# Sheet1.net
KiCad netlist of a schematic drawn in Altium Designer
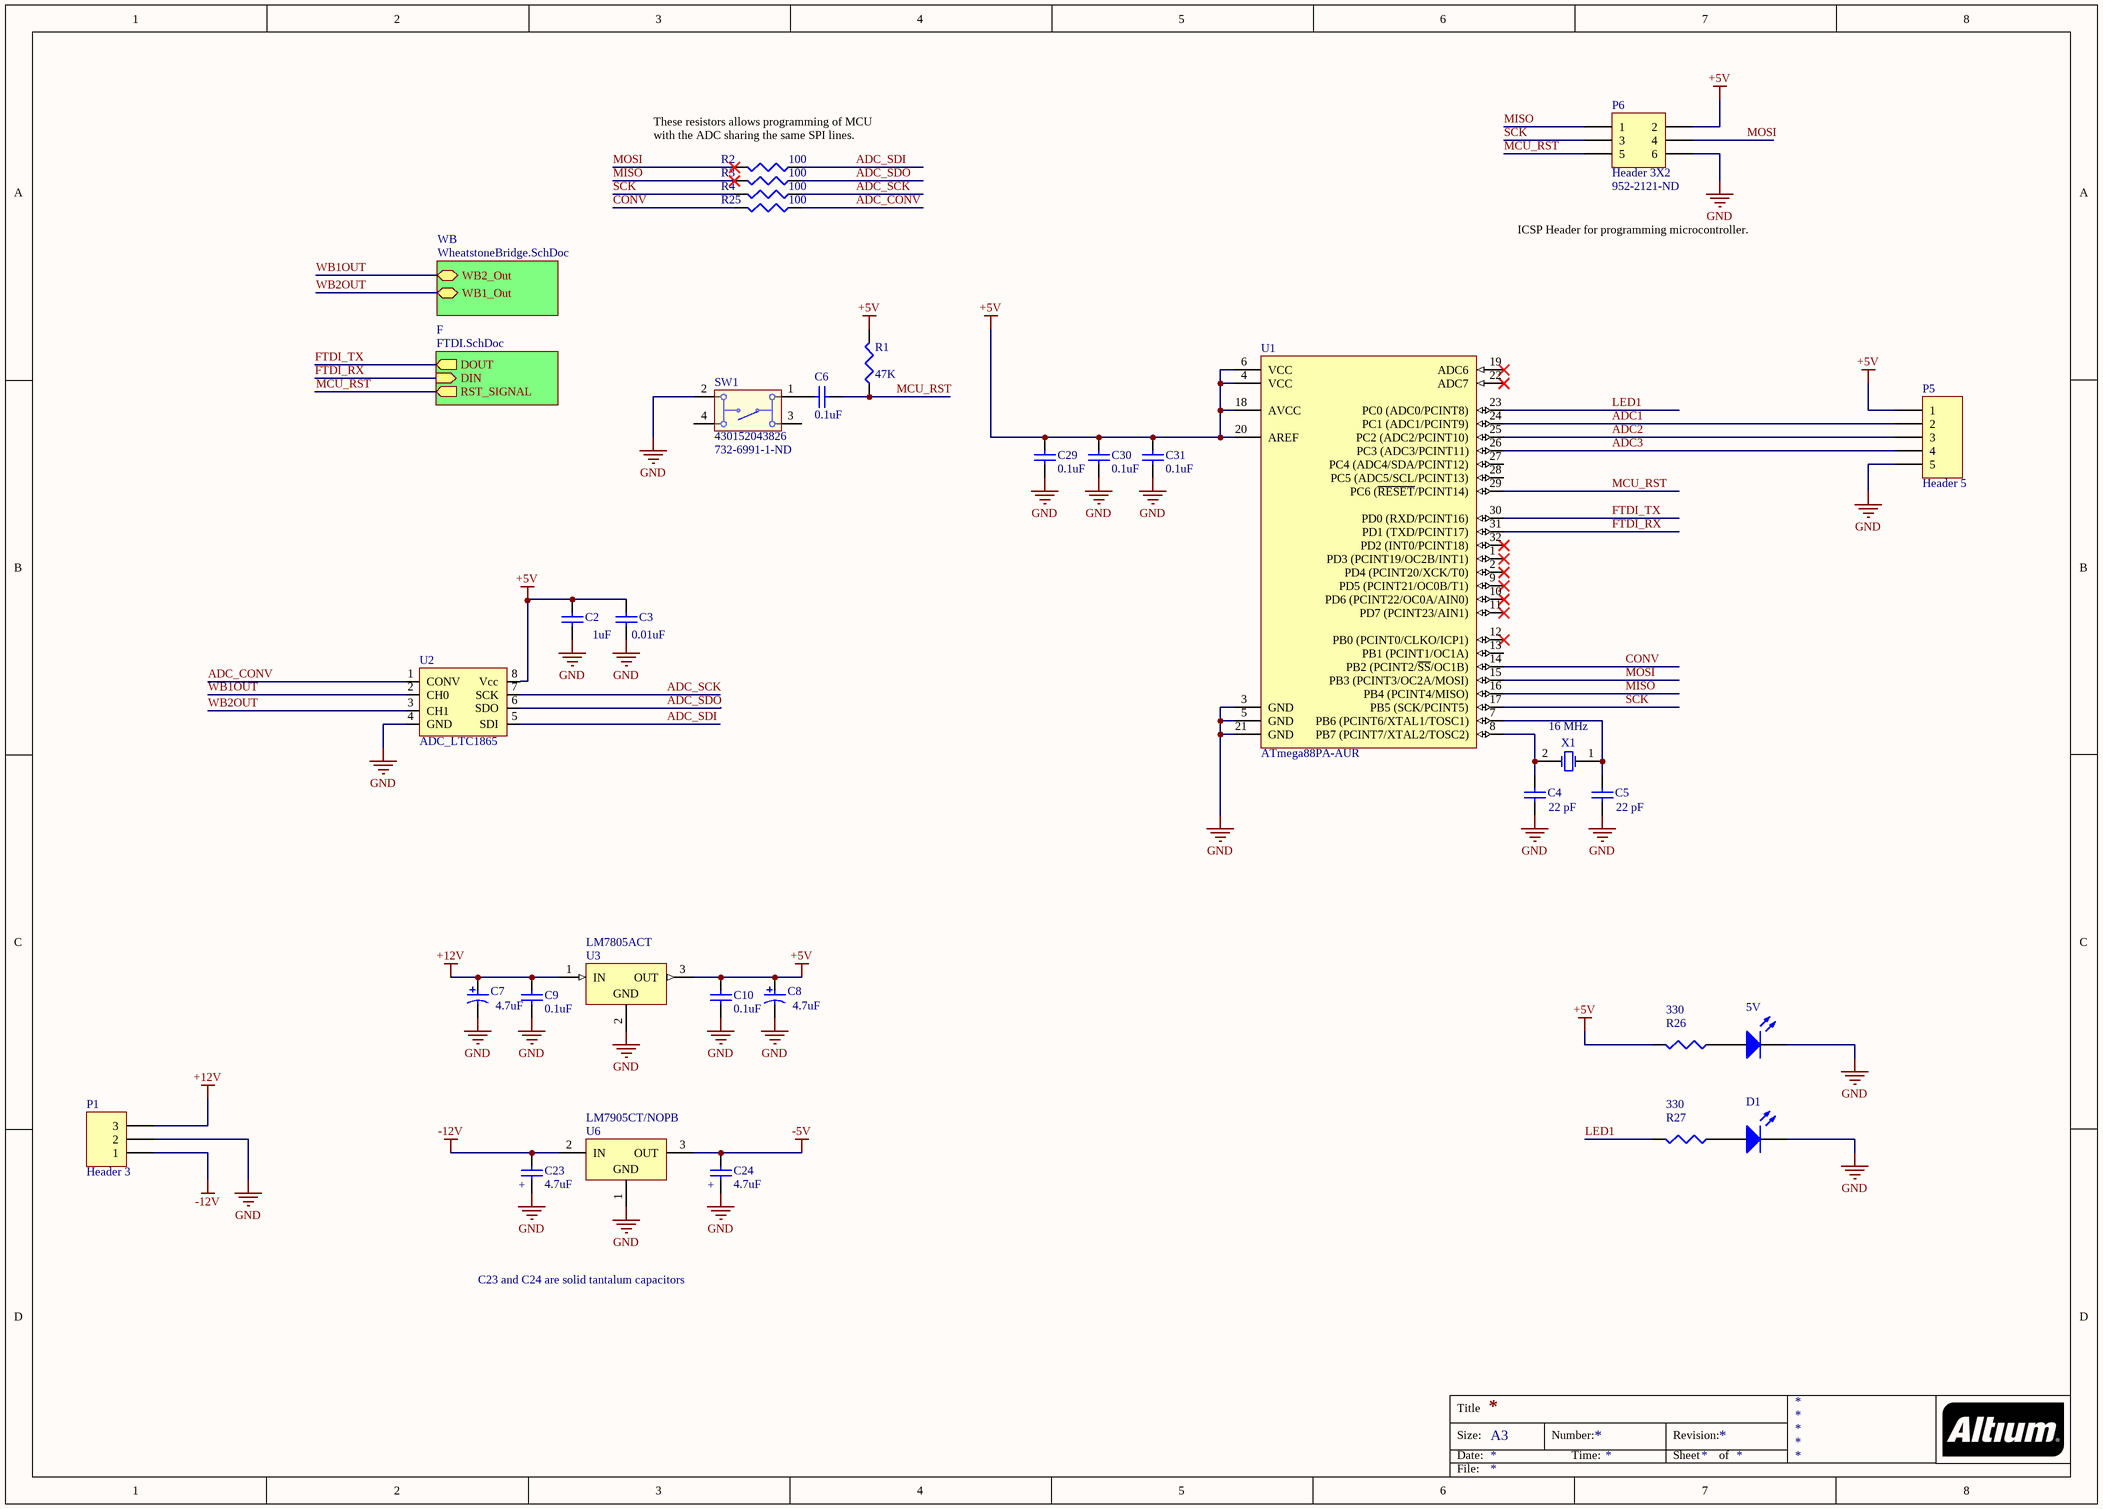
[diagram p0: Sheet1.SchDoc]

(export (version "E")
  (design (tool "Eeschema 10.0.6"))
  (components
    (comp (ref "5V")
      (value "150060RS75000")
      (footprint "0603_A")
      (description "SMD mono-color Chip LED, WL-SMCW, Red")
      (fields (field (name "MANUFACTURER") "Wuerth Elektronik"))
      (libsource (lib "Altium Content Vault") (part "CMP-1426-00001-1"))
    )
    (comp (ref "C2")
      (value "1uF")
      (footprint "1608[0603]")
      (description "Capacitor (Semiconductor SIM Model)")
      (fields (field (name "Comment") "Cap Semi") (field (name "PUBLISHER") "Altium Limited"))
      (libsource (lib "Miscellaneous Devices") (part "Cap Semi"))
    )
    (comp (ref "C3")
      (value "0.01uF")
      (footprint "1608[0603]")
      (description "Capacitor (Semiconductor SIM Model)")
      (fields (field (name "Comment") "Cap Semi") (field (name "PUBLISHER") "Altium Limited"))
      (libsource (lib "Miscellaneous Devices") (part "Cap Semi"))
    )
    (comp (ref "C4")
      (value "22 pF")
      (footprint "1608[0603]")
      (description "Capacitor (Semiconductor SIM Model)")
      (fields (field (name "Comment") "Cap Semi") (field (name "PUBLISHER") "Altium Limited"))
      (libsource (lib "Miscellaneous Devices") (part "Cap Semi"))
    )
    (comp (ref "C5")
      (value "22 pF")
      (footprint "1608[0603]")
      (description "Capacitor (Semiconductor SIM Model)")
      (fields (field (name "Comment") "Cap Semi") (field (name "PUBLISHER") "Altium Limited"))
      (libsource (lib "Miscellaneous Devices") (part "Cap Semi"))
    )
    (comp (ref "C6")
      (value "0.1uF")
      (footprint "1608[0603]")
      (description "Capacitor (Semiconductor SIM Model)")
      (fields (field (name "Comment") "Cap Semi") (field (name "PUBLISHER") "Altium Limited"))
      (libsource (lib "Miscellaneous Devices") (part "Cap Semi"))
    )
    (comp (ref "C7")
      (value "TAJA475K016RNJ")
      (footprint "AVX-TAJ-A-2_N")
      (description "Standard Tantalum, 4.7 uF, +/- 10%, 16 V, -55 to 125 degC, 2-Pin SMD (1206), RoHS, Tape and Reel")
      (fields
        (field (name "TOLERANCE") "10%")
        (field (name "VOLTAGE") "16V")
        (field (name "CAPACITANCE") "4.7uF")
      )
      (libsource (lib "Altium Content Vault") (part "CMP-2100-03687-1"))
    )
    (comp (ref "C8")
      (value "TAJA475K016RNJ")
      (footprint "AVX-TAJ-A-2_N")
      (description "Standard Tantalum, 4.7 uF, +/- 10%, 16 V, -55 to 125 degC, 2-Pin SMD (1206), RoHS, Tape and Reel")
      (fields
        (field (name "TOLERANCE") "10%")
        (field (name "VOLTAGE") "16V")
        (field (name "CAPACITANCE") "4.7uF")
      )
      (libsource (lib "Altium Content Vault") (part "CMP-2100-03687-1"))
    )
    (comp (ref "C9")
      (value "0.1uF")
      (footprint "1608[0603]")
      (description "Capacitor (Semiconductor SIM Model)")
      (fields (field (name "Comment") "Cap Semi") (field (name "PUBLISHER") "Altium Limited"))
      (libsource (lib "Miscellaneous Devices") (part "Cap Semi"))
    )
    (comp (ref "C10")
      (value "0.1uF")
      (footprint "1608[0603]")
      (description "Capacitor (Semiconductor SIM Model)")
      (fields (field (name "Comment") "Cap Semi") (field (name "PUBLISHER") "Altium Limited"))
      (libsource (lib "Miscellaneous Devices") (part "Cap Semi"))
    )
    (comp (ref "C23")
      (value "4.7uF")
      (footprint "1608[0603]")
      (description "Capacitor (Semiconductor SIM Model)")
      (fields (field (name "Comment") "Cap Semi") (field (name "PUBLISHER") "Altium Limited"))
      (libsource (lib "Miscellaneous Devices") (part "Cap Semi"))
    )
    (comp (ref "C24")
      (value "4.7uF")
      (footprint "1608[0603]")
      (description "Capacitor (Semiconductor SIM Model)")
      (fields (field (name "Comment") "Cap Semi") (field (name "PUBLISHER") "Altium Limited"))
      (libsource (lib "Miscellaneous Devices") (part "Cap Semi"))
    )
    (comp (ref "C29")
      (value "0.1uF")
      (footprint "1608[0603]")
      (description "Capacitor (Semiconductor SIM Model)")
      (fields (field (name "Comment") "Cap Semi") (field (name "PUBLISHER") "Altium Limited"))
      (libsource (lib "Miscellaneous Devices") (part "Cap Semi"))
    )
    (comp (ref "C30")
      (value "0.1uF")
      (footprint "1608[0603]")
      (description "Capacitor (Semiconductor SIM Model)")
      (fields (field (name "Comment") "Cap Semi") (field (name "PUBLISHER") "Altium Limited"))
      (libsource (lib "Miscellaneous Devices") (part "Cap Semi"))
    )
    (comp (ref "C31")
      (value "0.1uF")
      (footprint "1608[0603]")
      (description "Capacitor (Semiconductor SIM Model)")
      (fields (field (name "Comment") "Cap Semi") (field (name "PUBLISHER") "Altium Limited"))
      (libsource (lib "Miscellaneous Devices") (part "Cap Semi"))
    )
    (comp (ref "D1")
      (value "150060RS75000")
      (footprint "0603_A")
      (description "SMD mono-color Chip LED, WL-SMCW, Red")
      (fields (field (name "MANUFACTURER") "Wuerth Elektronik"))
      (libsource (lib "Altium Content Vault") (part "CMP-1426-00001-1"))
    )
    (comp (ref "P1")
      (value "Header 3")
      (footprint "HDR1X3")
      (description "Header, 3-Pin")
      (fields (field (name "PUBLISHER") "Altium Limited"))
      (libsource (lib "Miscellaneous Connectors") (part "Header 3"))
    )
    (comp (ref "P5")
      (value "Header 5")
      (footprint "HDR1X5")
      (description "Header, 5-Pin")
      (fields (field (name "PUBLISHER") "Altium Limited"))
      (libsource (lib "Miscellaneous Connectors") (part "Header 5"))
    )
    (comp (ref "P6")
      (value "Header 3X2")
      (footprint "HDR2X3")
      (description "Header, 3-Pin, Dual row")
      (fields
        (field (name "SUPPLIER PART NUMBER 1") "952-2121-ND")
        (field (name "PUBLISHER") "Altium Limited")
      )
      (libsource (lib "Miscellaneous Connectors") (part "Header 3X2"))
    )
    (comp (ref "R1")
      (value "47K")
      (footprint "J1-0603")
      (description "Resistor")
      (fields (field (name "Comment") "Res3") (field (name "PUBLISHER") "Altium Limited"))
      (libsource (lib "Miscellaneous Devices") (part "Res3"))
    )
    (comp (ref "R2")
      (value "100")
      (footprint "J1-0603")
      (description "Resistor")
      (fields (field (name "Comment") "Res3") (field (name "PUBLISHER") "Altium Limited"))
      (libsource (lib "Miscellaneous Devices") (part "Res3"))
    )
    (comp (ref "R3")
      (value "100")
      (footprint "J1-0603")
      (description "Resistor")
      (fields (field (name "Comment") "Res3") (field (name "PUBLISHER") "Altium Limited"))
      (libsource (lib "Miscellaneous Devices") (part "Res3"))
    )
    (comp (ref "R4")
      (value "100")
      (footprint "J1-0603")
      (description "Resistor")
      (fields (field (name "Comment") "Res3") (field (name "PUBLISHER") "Altium Limited"))
      (libsource (lib "Miscellaneous Devices") (part "Res3"))
    )
    (comp (ref "R25")
      (value "100")
      (footprint "J1-0603")
      (description "Resistor")
      (fields (field (name "Comment") "Res3") (field (name "PUBLISHER") "Altium Limited"))
      (libsource (lib "Miscellaneous Devices") (part "Res3"))
    )
    (comp (ref "R26")
      (value "330")
      (footprint "J1-0603")
      (description "Resistor")
      (fields (field (name "Comment") "Res3") (field (name "PUBLISHER") "Altium Limited"))
      (libsource (lib "Miscellaneous Devices") (part "Res3"))
    )
    (comp (ref "R27")
      (value "330")
      (footprint "J1-0603")
      (description "Resistor")
      (fields (field (name "Comment") "Res3") (field (name "PUBLISHER") "Altium Limited"))
      (libsource (lib "Miscellaneous Devices") (part "Res3"))
    )
    (comp (ref "SW1")
      (value "430152043826")
      (footprint "430152043826")
      (description "WS-TASV SMD Tact Switch 6X6 mm")
      (fields
        (field (name "MANUFACTURER") "Wuerth Elektronik")
        (field (name "SUPPLIER PART NUMBER 1") "732-6991-1-ND")
      )
      (libsource (lib "Altium Content Vault") (part "WE-TACT-SW-4"))
    )
    (comp (ref "U1")
      (value "ATmega88PA-AUR")
      (footprint "32A_N")
      (libsource (lib "Altium Content Vault") (part "MC-8B-ATM48-SQ32"))
    )
    (comp (ref "U2")
      (value "ADC_LTC1865")
      (footprint "PcbLib1:LTC1865_SOIC8")
      (libsource (lib "Schlib1") (part "ADC_LTC1865"))
    )
    (comp (ref "U3")
      (value "LM7805ACT")
      (footprint "FAIR-TO-220-3")
      (description "Positive Voltage Regulator, 5 V, 1 A, 0 to 125 degC, 3-Pin TO-220, RoHS, Tube")
      (fields (field (name "MANUFACTURER") "Fairchild"))
      (libsource (lib "Altium Content Vault") (part "FAIR-LM7805CT-TO220-3"))
    )
    (comp (ref "U6")
      (value "LM7905CT/NOPB")
      (footprint "NDE0003A")
      (description "3-Terminal Negative Regulator, 3-pin TO-220, Pb-Free")
      (fields (field (name "MANUFACTURER") "Texas Instruments"))
      (libsource (lib "Altium Content Vault") (part "PM-REG-LM7905-SIL3"))
    )
    (comp (ref "X1")
      (value "ABLS2-16.000MHZ-D4Y-T")
      (footprint "ABRA-ABLS2-2_V")
      (fields (field (name "MANUFACTURER") "Abracon") (field (name "FREQUENCY") "16 MHz"))
      (libsource (lib "Altium Content Vault") (part "CMP-0277-00002-1"))
    )
  )
  (nets
    (net (code "1") (name "+5V") (class "Default")
      (node (ref "C10") (pin "1") (pinfunction "1_1") (pintype "passive"))
      (node (ref "C2") (pin "1") (pinfunction "1_1") (pintype "passive"))
      (node (ref "C29") (pin "1") (pinfunction "1_1") (pintype "passive"))
      (node (ref "C3") (pin "1") (pinfunction "1_1") (pintype "passive"))
      (node (ref "C30") (pin "1") (pinfunction "1_1") (pintype "passive"))
      (node (ref "C31") (pin "1") (pinfunction "1_1") (pintype "passive"))
      (node (ref "C8") (pin "1") (pinfunction "1_1") (pintype "passive"))
      (node (ref "P5") (pin "1") (pinfunction "1_1") (pintype "passive"))
      (node (ref "P6") (pin "2") (pinfunction "2_2") (pintype "passive"))
      (node (ref "R1") (pin "2") (pinfunction "2_2") (pintype "passive"))
      (node (ref "R26") (pin "2") (pinfunction "2_2") (pintype "passive"))
      (node (ref "U1") (pin "18") (pinfunction "AVCC_18") (pintype "power_in"))
      (node (ref "U1") (pin "20") (pinfunction "AREF_20") (pintype "passive"))
      (node (ref "U1") (pin "4") (pinfunction "VCC_4") (pintype "power_in"))
      (node (ref "U1") (pin "6") (pinfunction "VCC_6") (pintype "power_in"))
      (node (ref "U2") (pin "8") (pinfunction "Vcc_8") (pintype "passive"))
      (node (ref "U3") (pin "3") (pinfunction "OUT_3") (pintype "output"))
    )
    (net (code "2") (name "+12V") (class "Default")
      (node (ref "C7") (pin "1") (pinfunction "1_1") (pintype "passive"))
      (node (ref "C9") (pin "1") (pinfunction "1_1") (pintype "passive"))
      (node (ref "P1") (pin "3") (pinfunction "3_3") (pintype "passive"))
      (node (ref "U3") (pin "1") (pinfunction "IN_1") (pintype "input"))
    )
    (net (code "3") (name "-5V") (class "Default")
      (node (ref "C24") (pin "1") (pinfunction "1_1") (pintype "passive"))
      (node (ref "U6") (pin "3") (pinfunction "OUT_3") (pintype "power_in"))
    )
    (net (code "4") (name "-12V") (class "Default")
      (node (ref "C23") (pin "1") (pinfunction "1_1") (pintype "passive"))
      (node (ref "P1") (pin "1") (pinfunction "1_1") (pintype "passive"))
      (node (ref "U6") (pin "2") (pinfunction "IN_2") (pintype "power_in"))
    )
    (net (code "5") (name "/ADC1") (class "Default")
      (node (ref "P5") (pin "2") (pinfunction "2_2") (pintype "passive"))
      (node (ref "U1") (pin "24") (pinfunction "PC1_(ADC1/PCINT9)_24") (pintype "bidirectional"))
    )
    (net (code "6") (name "/ADC2") (class "Default")
      (node (ref "P5") (pin "3") (pinfunction "3_3") (pintype "passive"))
      (node (ref "U1") (pin "25") (pinfunction "PC2_(ADC2/PCINT10)_25") (pintype "bidirectional"))
    )
    (net (code "7") (name "/ADC3") (class "Default")
      (node (ref "P5") (pin "4") (pinfunction "4_4") (pintype "passive"))
      (node (ref "U1") (pin "26") (pinfunction "PC3_(ADC3/PCINT11)_26") (pintype "bidirectional"))
    )
    (net (code "8") (name "/ADC_CONV") (class "Default")
      (node (ref "R25") (pin "1") (pinfunction "1_1") (pintype "passive"))
      (node (ref "U2") (pin "1") (pinfunction "CONV_1") (pintype "passive"))
    )
    (net (code "9") (name "/ADC_SCK") (class "Default")
      (node (ref "R4") (pin "1") (pinfunction "1_1") (pintype "passive"))
      (node (ref "U2") (pin "7") (pinfunction "SCK_7") (pintype "passive"))
    )
    (net (code "10") (name "/ADC_SDI") (class "Default")
      (node (ref "R2") (pin "1") (pinfunction "1_1") (pintype "passive"))
      (node (ref "U2") (pin "5") (pinfunction "SDI_5") (pintype "passive"))
    )
    (net (code "11") (name "/ADC_SDO") (class "Default")
      (node (ref "R3") (pin "1") (pinfunction "1_1") (pintype "passive"))
      (node (ref "U2") (pin "6") (pinfunction "SDO_6") (pintype "passive"))
    )
    (net (code "12") (name "/CONV") (class "Default")
      (node (ref "R25") (pin "2") (pinfunction "2_2") (pintype "passive"))
      (node (ref "U1") (pin "14") (pinfunction "PB2_(PCINT2/~{SS}/OC1B)_14") (pintype "bidirectional"))
    )
    (net (code "13") (name "/FTDI_RX") (class "Default")
      (node (ref "U1") (pin "31") (pinfunction "PD1_(TXD/PCINT17)_31") (pintype "bidirectional"))
    )
    (net (code "14") (name "/FTDI_TX") (class "Default")
      (node (ref "U1") (pin "30") (pinfunction "PD0_(RXD/PCINT16)_30") (pintype "bidirectional"))
    )
    (net (code "15") (name "/LED1") (class "Default")
      (node (ref "R27") (pin "2") (pinfunction "2_2") (pintype "passive"))
      (node (ref "U1") (pin "23") (pinfunction "PC0_(ADC0/PCINT8)_23") (pintype "bidirectional"))
    )
    (net (code "16") (name "/MCU_RST") (class "Default")
      (node (ref "C6") (pin "1") (pinfunction "1_1") (pintype "passive"))
      (node (ref "P6") (pin "5") (pinfunction "5_5") (pintype "passive"))
      (node (ref "R1") (pin "1") (pinfunction "1_1") (pintype "passive"))
      (node (ref "U1") (pin "29") (pinfunction "PC6_(~{RESET}/PCINT14)_29") (pintype "bidirectional"))
    )
    (net (code "17") (name "/MISO") (class "Default")
      (node (ref "P6") (pin "1") (pinfunction "1_1") (pintype "passive"))
      (node (ref "R3") (pin "2") (pinfunction "2_2") (pintype "passive"))
      (node (ref "U1") (pin "16") (pinfunction "PB4_(PCINT4/MISO)_16") (pintype "bidirectional"))
    )
    (net (code "18") (name "/MOSI") (class "Default")
      (node (ref "P6") (pin "4") (pinfunction "4_4") (pintype "passive"))
      (node (ref "R2") (pin "2") (pinfunction "2_2") (pintype "passive"))
      (node (ref "U1") (pin "15") (pinfunction "PB3_(PCINT3/OC2A/MOSI)_15") (pintype "bidirectional"))
    )
    (net (code "19") (name "/SCK") (class "Default")
      (node (ref "P6") (pin "3") (pinfunction "3_3") (pintype "passive"))
      (node (ref "R4") (pin "2") (pinfunction "2_2") (pintype "passive"))
      (node (ref "U1") (pin "17") (pinfunction "PB5_(SCK/PCINT5)_17") (pintype "bidirectional"))
    )
    (net (code "20") (name "/WB1OUT") (class "Default")
      (node (ref "U2") (pin "2") (pinfunction "CH0_2") (pintype "passive"))
    )
    (net (code "21") (name "/WB2OUT") (class "Default")
      (node (ref "U2") (pin "3") (pinfunction "CH1_3") (pintype "passive"))
    )
    (net (code "22") (name "GND") (class "Default")
      (node (ref "5V") (pin "1") (pinfunction "K_1") (pintype "passive"))
      (node (ref "C10") (pin "2") (pinfunction "2_2") (pintype "passive"))
      (node (ref "C2") (pin "2") (pinfunction "2_2") (pintype "passive"))
      (node (ref "C23") (pin "2") (pinfunction "2_2") (pintype "passive"))
      (node (ref "C24") (pin "2") (pinfunction "2_2") (pintype "passive"))
      (node (ref "C29") (pin "2") (pinfunction "2_2") (pintype "passive"))
      (node (ref "C3") (pin "2") (pinfunction "2_2") (pintype "passive"))
      (node (ref "C30") (pin "2") (pinfunction "2_2") (pintype "passive"))
      (node (ref "C31") (pin "2") (pinfunction "2_2") (pintype "passive"))
      (node (ref "C4") (pin "1") (pinfunction "1_1") (pintype "passive"))
      (node (ref "C5") (pin "1") (pinfunction "1_1") (pintype "passive"))
      (node (ref "C7") (pin "2") (pinfunction "2_2") (pintype "passive"))
      (node (ref "C8") (pin "2") (pinfunction "2_2") (pintype "passive"))
      (node (ref "C9") (pin "2") (pinfunction "2_2") (pintype "passive"))
      (node (ref "D1") (pin "1") (pinfunction "K_1") (pintype "passive"))
      (node (ref "P1") (pin "2") (pinfunction "2_2") (pintype "passive"))
      (node (ref "P5") (pin "5") (pinfunction "5_5") (pintype "passive"))
      (node (ref "P6") (pin "6") (pinfunction "6_6") (pintype "passive"))
      (node (ref "SW1") (pin "2") (pinfunction "2_2") (pintype "passive"))
      (node (ref "U1") (pin "21") (pinfunction "GND_21") (pintype "power_in"))
      (node (ref "U1") (pin "3") (pinfunction "GND_3") (pintype "power_in"))
      (node (ref "U1") (pin "5") (pinfunction "GND_5") (pintype "power_in"))
      (node (ref "U2") (pin "4") (pinfunction "GND_4") (pintype "passive"))
      (node (ref "U3") (pin "2") (pinfunction "GND_2") (pintype "power_in"))
      (node (ref "U6") (pin "1") (pinfunction "GND_1") (pintype "power_in"))
    )
    (net (code "23") (name "Net-(5V-A)") (class "Default")
      (node (ref "5V") (pin "2") (pinfunction "A_2") (pintype "passive"))
      (node (ref "R26") (pin "1") (pinfunction "1_1") (pintype "passive"))
    )
    (net (code "24") (name "Net-(C6-Pad2)") (class "Default")
      (node (ref "C6") (pin "2") (pinfunction "2_2") (pintype "passive"))
      (node (ref "SW1") (pin "1") (pinfunction "1_1") (pintype "passive"))
    )
    (net (code "25") (name "Net-(D1-A)") (class "Default")
      (node (ref "D1") (pin "2") (pinfunction "A_2") (pintype "passive"))
      (node (ref "R27") (pin "1") (pinfunction "1_1") (pintype "passive"))
    )
    (net (code "26") (name "Net-(U1-PB6_(PCINT6{slash}XTAL1{slash}TOSC1))") (class "Default")
      (node (ref "C5") (pin "2") (pinfunction "2_2") (pintype "passive"))
      (node (ref "U1") (pin "7") (pinfunction "PB6_(PCINT6/XTAL1/TOSC1)_7") (pintype "bidirectional"))
      (node (ref "X1") (pin "1") (pinfunction "X1_1") (pintype "passive"))
    )
    (net (code "27") (name "Net-(U1-PB7_(PCINT7{slash}XTAL2{slash}TOSC2))") (class "Default")
      (node (ref "C4") (pin "2") (pinfunction "2_2") (pintype "passive"))
      (node (ref "U1") (pin "8") (pinfunction "PB7_(PCINT7/XTAL2/TOSC2)_8") (pintype "bidirectional"))
      (node (ref "X1") (pin "2") (pinfunction "X2_2") (pintype "passive"))
    )
    (net (code "28") (name "unconnected-(SW1-Pad3)") (class "Default")
      (node (ref "SW1") (pin "3") (pinfunction "3_3") (pintype "passive"))
    )
    (net (code "29") (name "unconnected-(SW1-Pad4)") (class "Default")
      (node (ref "SW1") (pin "4") (pinfunction "4_4") (pintype "passive"))
    )
    (net (code "30") (name "unconnected-(U1-ADC6-Pad19)") (class "Default")
      (node (ref "U1") (pin "19") (pinfunction "ADC6_19") (pintype "input+no_connect"))
    )
    (net (code "31") (name "unconnected-(U1-ADC7-Pad22)") (class "Default")
      (node (ref "U1") (pin "22") (pinfunction "ADC7_22") (pintype "input+no_connect"))
    )
    (net (code "32") (name "unconnected-(U1-PB0_(PCINT0{slash}CLKO{slash}ICP1)-Pad12)") (class "Default")
      (node (ref "U1") (pin "12") (pinfunction "PB0_(PCINT0/CLKO/ICP1)_12") (pintype "bidirectional+no_connect"))
    )
    (net (code "33") (name "unconnected-(U1-PB1_(PCINT1{slash}OC1A)-Pad13)") (class "Default")
      (node (ref "U1") (pin "13") (pinfunction "PB1_(PCINT1/OC1A)_13") (pintype "bidirectional"))
    )
    (net (code "34") (name "unconnected-(U1-PC4_(ADC4{slash}SDA{slash}PCINT12)-Pad27)") (class "Default")
      (node (ref "U1") (pin "27") (pinfunction "PC4_(ADC4/SDA/PCINT12)_27") (pintype "bidirectional"))
    )
    (net (code "35") (name "unconnected-(U1-PC5_(ADC5{slash}SCL{slash}PCINT13)-Pad28)") (class "Default")
      (node (ref "U1") (pin "28") (pinfunction "PC5_(ADC5/SCL/PCINT13)_28") (pintype "bidirectional"))
    )
    (net (code "36") (name "unconnected-(U1-PD2_(INT0{slash}PCINT18)-Pad32)") (class "Default")
      (node (ref "U1") (pin "32") (pinfunction "PD2_(INT0/PCINT18)_32") (pintype "bidirectional+no_connect"))
    )
    (net (code "37") (name "unconnected-(U1-PD3_(PCINT19{slash}OC2B{slash}INT1)-Pad1)") (class "Default")
      (node (ref "U1") (pin "1") (pinfunction "PD3_(PCINT19/OC2B/INT1)_1") (pintype "bidirectional+no_connect"))
    )
    (net (code "38") (name "unconnected-(U1-PD4_(PCINT20{slash}XCK{slash}T0)-Pad2)") (class "Default")
      (node (ref "U1") (pin "2") (pinfunction "PD4_(PCINT20/XCK/T0)_2") (pintype "bidirectional+no_connect"))
    )
    (net (code "39") (name "unconnected-(U1-PD5_(PCINT21{slash}OC0B{slash}T1)-Pad9)") (class "Default")
      (node (ref "U1") (pin "9") (pinfunction "PD5_(PCINT21/OC0B/T1)_9") (pintype "bidirectional+no_connect"))
    )
    (net (code "40") (name "unconnected-(U1-PD6_(PCINT22{slash}OC0A{slash}AIN0)-Pad10)") (class "Default")
      (node (ref "U1") (pin "10") (pinfunction "PD6_(PCINT22/OC0A/AIN0)_10") (pintype "bidirectional+no_connect"))
    )
    (net (code "41") (name "unconnected-(U1-PD7_(PCINT23{slash}AIN1)-Pad11)") (class "Default")
      (node (ref "U1") (pin "11") (pinfunction "PD7_(PCINT23/AIN1)_11") (pintype "bidirectional+no_connect"))
    )
  )
)
